# LCDTFTPWR_AP3031.net
KiCad netlist of a schematic drawn in Altium Designer
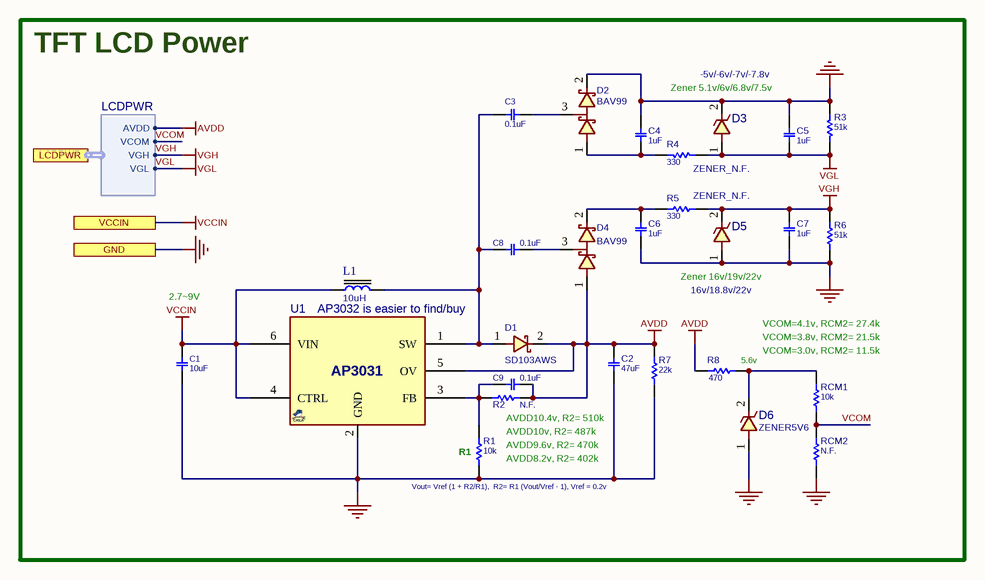
[diagram p0: LCDTFTPWR_AP3031.SchDoc]

(export (version "E")
  (design (tool "Eeschema 10.0.6"))
  (components
    (comp (ref "C1")
      (value "10uF")
      (footprint "C0402")
      (description "CAP, MLCC")
      (fields (field (name "MANF_P#") "CL10A106MO8NQNC") (field (name "MANF") "Samsung"))
      (libsource (lib "passive_smd") (part "CAP_SMD_MLCC"))
    )
    (comp (ref "C2")
      (value "47uF")
      (footprint "C1206")
      (description "CAP, MLCC")
      (fields (field (name "MANF_P#") "GRM31CR61E476ME44L") (field (name "MANF") "Murata"))
      (libsource (lib "passive_smd") (part "CAP_SMD_MLCC"))
    )
    (comp (ref "C3")
      (value "0.1uF")
      (footprint "C0402")
      (description "CAP, MLCC, 100nF, 50V, X7R, 10%, 0402C")
      (fields (field (name "MANF") "Murata") (field (name "MANF_P#") "GCM155R71H104KE02D"))
      (libsource (lib "passive_mlcc_smd") (part "CAP_SMD_MLCC_100n50V"))
    )
    (comp (ref "C4")
      (value "1uF")
      (footprint "C0603")
      (description "CAP, MLCC")
      (fields (field (name "MANF_P#") "CL10A105KB8NNNC") (field (name "MANF") "Samsung"))
      (libsource (lib "passive_smd") (part "CAP_SMD_MLCC"))
    )
    (comp (ref "C5")
      (value "1uF")
      (footprint "C0603")
      (description "CAP, MLCC")
      (fields (field (name "MANF_P#") "CL10A105KB8NNNC") (field (name "MANF") "Samsung"))
      (libsource (lib "passive_smd") (part "CAP_SMD_MLCC"))
    )
    (comp (ref "C6")
      (value "1uF")
      (footprint "C0603")
      (description "CAP, MLCC")
      (fields (field (name "MANF_P#") "CL10A105KB8NNNC") (field (name "MANF") "Samsung"))
      (libsource (lib "passive_smd") (part "CAP_SMD_MLCC"))
    )
    (comp (ref "C7")
      (value "1uF")
      (footprint "C0603")
      (description "CAP, MLCC")
      (fields (field (name "MANF_P#") "CL10A105KB8NNNC") (field (name "MANF") "Samsung"))
      (libsource (lib "passive_smd") (part "CAP_SMD_MLCC"))
    )
    (comp (ref "C8")
      (value "0.1uF")
      (footprint "C0402")
      (description "CAP, MLCC, 100nF, 50V, X7R, 10%, 0402C")
      (fields (field (name "MANF") "Murata") (field (name "MANF_P#") "GCM155R71H104KE02D"))
      (libsource (lib "passive_mlcc_smd") (part "CAP_SMD_MLCC_100n50V"))
    )
    (comp (ref "C9")
      (value "0.1uF")
      (footprint "C0402")
      (description "CAP, MLCC, 100nF, 50V, X7R, 10%, 0402C")
      (fields (field (name "MANF") "Murata") (field (name "MANF_P#") "GCM155R71H104KE02D"))
      (libsource (lib "passive_mlcc_smd") (part "CAP_SMD_MLCC_100n50V"))
    )
    (comp (ref "D1")
      (value "SD103AWS")
      (footprint "D_SOD323")
      (description "DIODE, SCHOTTKY, 40V, 2A")
      (fields (field (name "MANF") "DIODES"))
      (libsource (lib "diode") (part "DIODE_SMD_SCHOTTKY_1N5819"))
    )
    (comp (ref "D2")
      (value "BAV99")
      (footprint "SOT23_3")
      (description "DIODE, SCHOTTKY, DUAL, 30V, 0.2A")
      (fields (field (name "MANF") "Diodes"))
      (libsource (lib "diode") (part "DIODE_SMD_SCHOTTKY_BAV99"))
    )
    (comp (ref "D3")
      (value "ZENER_N.F.")
      (footprint "D_SOD123W")
      (description "DIODE, ZENER, 0.5W")
      (fields (field (name "MANF") "Diodes"))
      (libsource (lib "diode") (part "DIODE_SMD_ZENER_DFLZ5V1"))
    )
    (comp (ref "D4")
      (value "BAV99")
      (footprint "SOT23_3")
      (description "DIODE, SCHOTTKY, DUAL, 30V, 0.2A")
      (fields (field (name "MANF") "Diodes"))
      (libsource (lib "diode") (part "DIODE_SMD_SCHOTTKY_BAV99"))
    )
    (comp (ref "D5")
      (value "ZENER_N.F.")
      (footprint "D_SOD123W")
      (description "DIODE, ZENER, 0.5W")
      (fields (field (name "MANF") "Diodes"))
      (libsource (lib "diode") (part "DIODE_SMD_ZENER_DFLZ5V1"))
    )
    (comp (ref "D6")
      (value "ZENER5V6")
      (footprint "D_SOD123W")
      (description "DIODE, ZENER, 0.5W")
      (fields (field (name "MANF") "Diodes"))
      (libsource (lib "diode") (part "DIODE_SMD_ZENER_DFLZ5V1"))
    )
    (comp (ref "L1")
      (value "10uH")
      (footprint "L_4")
      (description "INDUCTOR, POWER, SMD")
      (fields (field (name "MANF_P#") "GCD43-100MC"))
      (libsource (lib "passive") (part "INDPWR_SMD"))
    )
    (comp (ref "R1")
      (value "10k")
      (footprint "R0402")
      (description "RESISTOR, SMD, 20K, 0402")
      (fields (field (name "MANF") "Yageo") (field (name "MANF_P#") "RK73H1ETTP2002F"))
      (libsource (lib "chila_passive") (part "RES_SMD"))
    )
    (comp (ref "R2")
      (value "N.F.")
      (footprint "R0402")
      (description "RESISTOR, SMD, 20K, 0402")
      (fields (field (name "MANF") "Yageo") (field (name "MANF_P#") "RK73H1ETTP2002F"))
      (libsource (lib "chila_passive") (part "RES_SMD"))
    )
    (comp (ref "R3")
      (value "51k")
      (footprint "R0402")
      (description "RESISTOR, SMD, 20K, 0402")
      (fields (field (name "MANF") "Yageo") (field (name "MANF_P#") "RK73H1ETTP2002F"))
      (libsource (lib "chila_passive") (part "RES_SMD"))
    )
    (comp (ref "R4")
      (value "330")
      (footprint "R0402")
      (description "RESISTOR, SMD, 20K, 0402")
      (fields (field (name "MANF") "Yageo") (field (name "MANF_P#") "RK73H1ETTP2002F"))
      (libsource (lib "chila_passive") (part "RES_SMD"))
    )
    (comp (ref "R5")
      (value "330")
      (footprint "R0402")
      (description "RESISTOR, SMD, 20K, 0402")
      (fields (field (name "MANF") "Yageo") (field (name "MANF_P#") "RK73H1ETTP2002F"))
      (libsource (lib "chila_passive") (part "RES_SMD"))
    )
    (comp (ref "R6")
      (value "51k")
      (footprint "R0402")
      (description "RESISTOR, SMD, 20K, 0402")
      (fields (field (name "MANF") "Yageo") (field (name "MANF_P#") "RK73H1ETTP2002F"))
      (libsource (lib "chila_passive") (part "RES_SMD"))
    )
    (comp (ref "R7")
      (value "22k")
      (footprint "R0402")
      (description "RESISTOR, SMD, 20K, 0402")
      (fields (field (name "MANF") "Yageo") (field (name "MANF_P#") "RK73H1ETTP2002F"))
      (libsource (lib "chila_passive") (part "RES_SMD"))
    )
    (comp (ref "R8")
      (value "470")
      (footprint "R0402")
      (description "RESISTOR, SMD, 20K, 0402")
      (fields (field (name "MANF") "Yageo") (field (name "MANF_P#") "RK73H1ETTP2002F"))
      (libsource (lib "chila_passive") (part "RES_SMD"))
    )
    (comp (ref "RCM1")
      (value "10k")
      (footprint "R0402")
      (description "RESISTOR, SMD, 20K, 0402")
      (fields (field (name "MANF") "Yageo") (field (name "MANF_P#") "RK73H1ETTP2002F"))
      (libsource (lib "chila_passive") (part "RES_SMD"))
    )
    (comp (ref "RCM2")
      (value "N.F.")
      (footprint "R0402")
      (description "RESISTOR, SMD, 20K, 0402")
      (fields (field (name "MANF") "Yageo") (field (name "MANF_P#") "RK73H1ETTP2002F"))
      (libsource (lib "chila_passive") (part "RES_SMD"))
    )
    (comp (ref "U1")
      (value "AP3031")
      (footprint "SOT23_6")
      (description "REG, Switching, Boost, 1.4A, ADJ, 1MHz, SOT-23-6")
      (fields (field (name "MANF_P#") "AP3031K") (field (name "MANF") "Diodes"))
      (libsource (lib "pwr_switching_boost") (part "VREG_AP3031_SOT23"))
    )
  )
  (nets
    (net (code "2") (name "/VCOM") (class "Default")
      (node (ref "RCM1") (pin "2") (pinfunction "2_2") (pintype "passive"))
      (node (ref "RCM2") (pin "1") (pinfunction "1_1") (pintype "passive"))
    )
    (net (code "4") (name "AVDD") (class "Default")
      (node (ref "C2") (pin "2") (pinfunction "2_2") (pintype "passive"))
      (node (ref "C9") (pin "1") (pinfunction "1_1") (pintype "passive"))
      (node (ref "D1") (pin "2") (pinfunction "2_2") (pintype "passive"))
      (node (ref "D4") (pin "1") (pinfunction "1_1") (pintype "passive"))
      (node (ref "R2") (pin "2") (pinfunction "2_2") (pintype "passive"))
      (node (ref "R7") (pin "1") (pinfunction "1_1") (pintype "passive"))
      (node (ref "R8") (pin "1") (pinfunction "1_1") (pintype "passive"))
      (node (ref "U1") (pin "5") (pinfunction "OV_5") (pintype "passive"))
    )
    (net (code "5") (name "GND") (class "Default")
      (node (ref "C1") (pin "1") (pinfunction "1_1") (pintype "passive"))
      (node (ref "C2") (pin "1") (pinfunction "1_1") (pintype "passive"))
      (node (ref "C4") (pin "1") (pinfunction "1_1") (pintype "passive"))
      (node (ref "C5") (pin "1") (pinfunction "1_1") (pintype "passive"))
      (node (ref "C6") (pin "1") (pinfunction "1_1") (pintype "passive"))
      (node (ref "C7") (pin "1") (pinfunction "1_1") (pintype "passive"))
      (node (ref "D2") (pin "2") (pinfunction "2_2") (pintype "passive"))
      (node (ref "D3") (pin "2") (pinfunction "2_2") (pintype "passive"))
      (node (ref "D5") (pin "1") (pinfunction "1_1") (pintype "passive"))
      (node (ref "D6") (pin "1") (pinfunction "1_1") (pintype "passive"))
      (node (ref "R1") (pin "2") (pinfunction "2_2") (pintype "passive"))
      (node (ref "R3") (pin "1") (pinfunction "1_1") (pintype "passive"))
      (node (ref "R6") (pin "1") (pinfunction "1_1") (pintype "passive"))
      (node (ref "R7") (pin "2") (pinfunction "2_2") (pintype "passive"))
      (node (ref "RCM2") (pin "2") (pinfunction "2_2") (pintype "passive"))
      (node (ref "U1") (pin "2") (pinfunction "GND_2") (pintype "tri_state"))
    )
    (net (code "6") (name "Net-(C3-Pad1)") (class "Default")
      (node (ref "C3") (pin "1") (pinfunction "1_1") (pintype "passive"))
      (node (ref "D2") (pin "3") (pinfunction "3_3") (pintype "passive"))
    )
    (net (code "7") (name "Net-(C4-Pad2)") (class "Default")
      (node (ref "C4") (pin "2") (pinfunction "2_2") (pintype "passive"))
      (node (ref "D2") (pin "1") (pinfunction "1_1") (pintype "passive"))
      (node (ref "R4") (pin "1") (pinfunction "1_1") (pintype "passive"))
    )
    (net (code "8") (name "Net-(C6-Pad2)") (class "Default")
      (node (ref "C6") (pin "2") (pinfunction "2_2") (pintype "passive"))
      (node (ref "D4") (pin "2") (pinfunction "2_2") (pintype "passive"))
      (node (ref "R5") (pin "1") (pinfunction "1_1") (pintype "passive"))
    )
    (net (code "9") (name "Net-(C8-Pad1)") (class "Default")
      (node (ref "C8") (pin "1") (pinfunction "1_1") (pintype "passive"))
      (node (ref "D4") (pin "3") (pinfunction "3_3") (pintype "passive"))
    )
    (net (code "10") (name "Net-(D6-Pad2)") (class "Default")
      (node (ref "D6") (pin "2") (pinfunction "2_2") (pintype "passive"))
      (node (ref "R8") (pin "2") (pinfunction "2_2") (pintype "passive"))
      (node (ref "RCM1") (pin "1") (pinfunction "1_1") (pintype "passive"))
    )
    (net (code "11") (name "Net-(U1-FB)") (class "Default")
      (node (ref "C9") (pin "2") (pinfunction "2_2") (pintype "passive"))
      (node (ref "R1") (pin "1") (pinfunction "1_1") (pintype "passive"))
      (node (ref "R2") (pin "1") (pinfunction "1_1") (pintype "passive"))
      (node (ref "U1") (pin "3") (pinfunction "FB_3") (pintype "passive"))
    )
    (net (code "12") (name "Net-(U1-SW)") (class "Default")
      (node (ref "C3") (pin "2") (pinfunction "2_2") (pintype "passive"))
      (node (ref "C8") (pin "2") (pinfunction "2_2") (pintype "passive"))
      (node (ref "D1") (pin "1") (pinfunction "1_1") (pintype "passive"))
      (node (ref "L1") (pin "2") (pinfunction "2_2") (pintype "passive"))
      (node (ref "U1") (pin "1") (pinfunction "SW_1") (pintype "passive"))
    )
    (net (code "13") (name "VCCIN") (class "Default")
      (node (ref "C1") (pin "2") (pinfunction "2_2") (pintype "passive"))
      (node (ref "L1") (pin "1") (pinfunction "1_1") (pintype "passive"))
      (node (ref "U1") (pin "4") (pinfunction "CTRL_4") (pintype "passive"))
      (node (ref "U1") (pin "6") (pinfunction "VIN_6") (pintype "passive"))
    )
    (net (code "14") (name "VGH") (class "Default")
      (node (ref "C7") (pin "2") (pinfunction "2_2") (pintype "passive"))
      (node (ref "D5") (pin "2") (pinfunction "2_2") (pintype "passive"))
      (node (ref "R5") (pin "2") (pinfunction "2_2") (pintype "passive"))
      (node (ref "R6") (pin "2") (pinfunction "2_2") (pintype "passive"))
    )
    (net (code "15") (name "VGL") (class "Default")
      (node (ref "C5") (pin "2") (pinfunction "2_2") (pintype "passive"))
      (node (ref "D3") (pin "1") (pinfunction "1_1") (pintype "passive"))
      (node (ref "R3") (pin "2") (pinfunction "2_2") (pintype "passive"))
      (node (ref "R4") (pin "2") (pinfunction "2_2") (pintype "passive"))
    )
  )
)
